# STM32Fx.net
KiCad netlist of a schematic drawn in Altium Designer
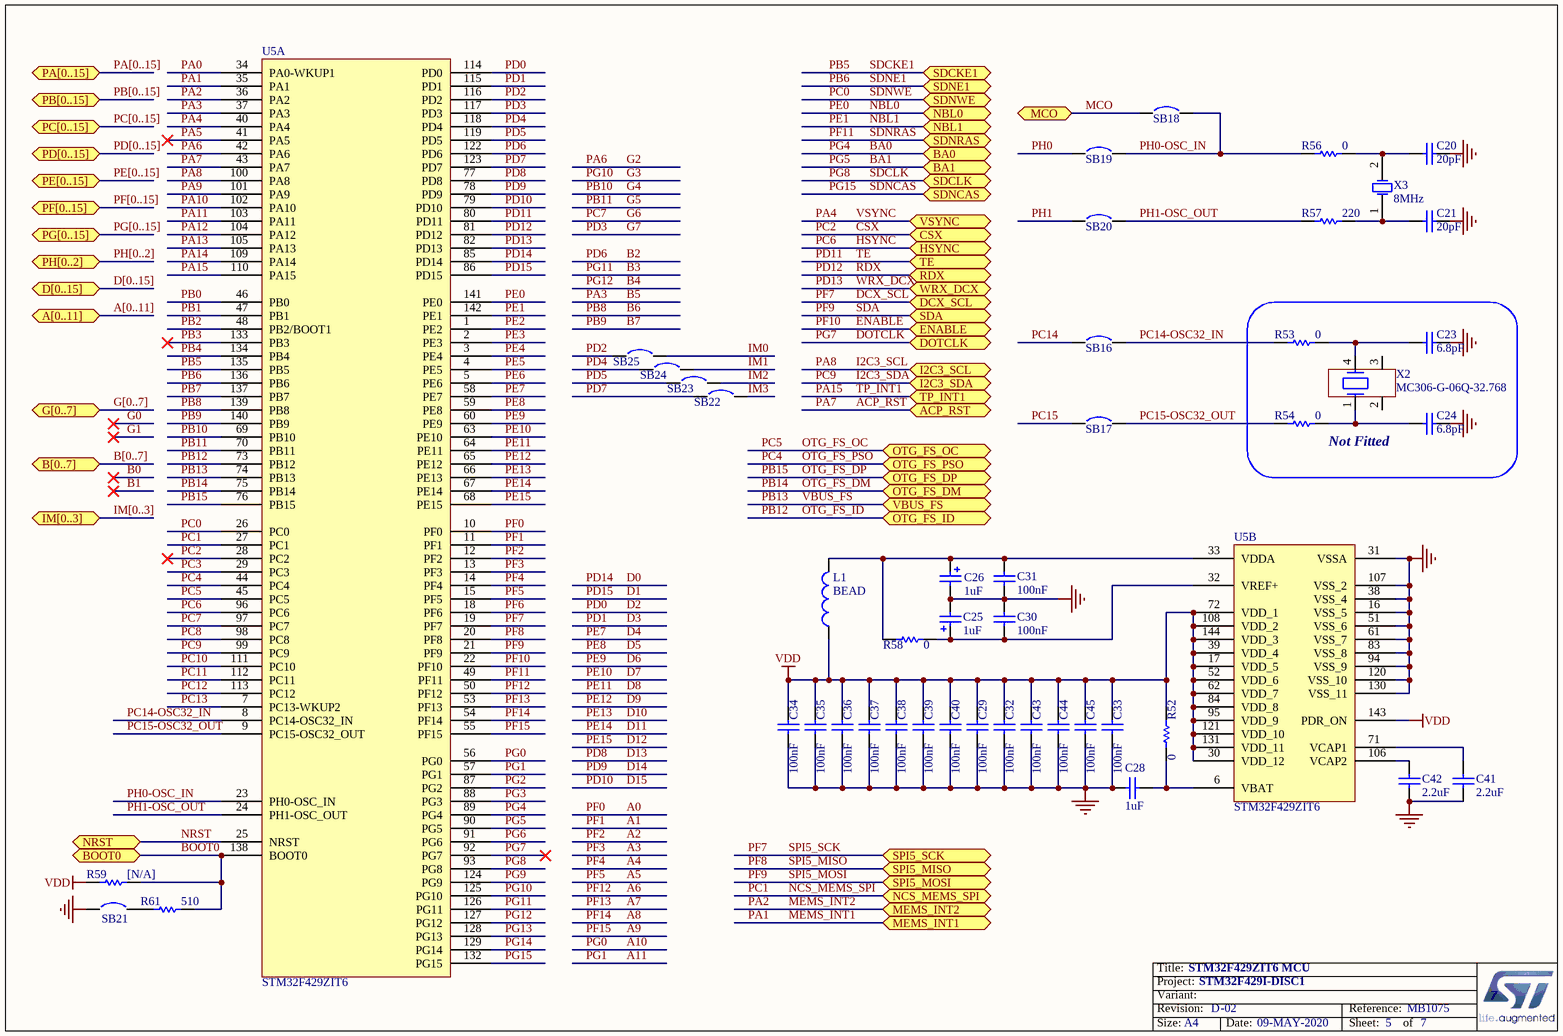
[diagram p0: STM32Fx.SchDoc]

(export (version "E")
  (design (tool "Eeschema 10.0.6"))
  (components
    (comp (ref "C20")
      (value "20pF")
      (footprint "0402C")
      (description "Capacitor 0402 / 0603 / 0805")
      (libsource (lib "MCD_TOOLS") (part "Capacitor_ST"))
    )
    (comp (ref "C21")
      (value "20pF")
      (footprint "0402C")
      (description "Capacitor 0402 / 0603 / 0805")
      (libsource (lib "MCD_TOOLS") (part "Capacitor_ST"))
    )
    (comp (ref "C23")
      (value "6.8pF")
      (footprint "0402C")
      (description "Capacitor 0402 / 0603 / 0805")
      (libsource (lib "MCD_TOOLS") (part "Capacitor_ST"))
    )
    (comp (ref "C24")
      (value "6.8pF")
      (footprint "0402C")
      (description "Capacitor 0402 / 0603 / 0805")
      (libsource (lib "MCD_TOOLS") (part "Capacitor_ST"))
    )
    (comp (ref "C25")
      (value "1uF")
      (footprint "TAN-A")
      (description "Polarized Capacitor (Radial)")
      (fields (field (name "PUBLISHER") "Altium Limited"))
      (libsource (lib "Miscellaneous Devices") (part "Cap Pol1"))
    )
    (comp (ref "C26")
      (value "1uF")
      (footprint "TAN-A")
      (description "Polarized Capacitor (Radial)")
      (fields (field (name "PUBLISHER") "Altium Limited"))
      (libsource (lib "Miscellaneous Devices") (part "Cap Pol1"))
    )
    (comp (ref "C28")
      (value "1uF")
      (footprint "0603C")
      (description "Capacitor 0402 / 0603 / 0805")
      (libsource (lib "MCD_TOOLS") (part "Capacitor_ST"))
    )
    (comp (ref "C29")
      (value "100nF")
      (footprint "0402C")
      (description "Capacitor 0402 / 0603 / 0805")
      (libsource (lib "MCD_TOOLS") (part "Capacitor_ST"))
    )
    (comp (ref "C30")
      (value "100nF")
      (footprint "0402C")
      (description "Capacitor 0402 / 0603 / 0805")
      (libsource (lib "MCD_TOOLS") (part "Capacitor_ST"))
    )
    (comp (ref "C31")
      (value "100nF")
      (footprint "0402C")
      (description "Capacitor 0402 / 0603 / 0805")
      (libsource (lib "MCD_TOOLS") (part "Capacitor_ST"))
    )
    (comp (ref "C32")
      (value "100nF")
      (footprint "0402C")
      (description "Capacitor 0402 / 0603 / 0805")
      (libsource (lib "MCD_TOOLS") (part "Capacitor_ST"))
    )
    (comp (ref "C33")
      (value "100nF")
      (footprint "0402C")
      (description "Capacitor 0402 / 0603 / 0805")
      (libsource (lib "MCD_TOOLS") (part "Capacitor_ST"))
    )
    (comp (ref "C34")
      (value "100nF")
      (footprint "0402C")
      (description "Capacitor 0402 / 0603 / 0805")
      (libsource (lib "MCD_TOOLS") (part "Capacitor_ST"))
    )
    (comp (ref "C35")
      (value "100nF")
      (footprint "0402C")
      (description "Capacitor 0402 / 0603 / 0805")
      (libsource (lib "MCD_TOOLS") (part "Capacitor_ST"))
    )
    (comp (ref "C36")
      (value "100nF")
      (footprint "0402C")
      (description "Capacitor 0402 / 0603 / 0805")
      (libsource (lib "MCD_TOOLS") (part "Capacitor_ST"))
    )
    (comp (ref "C37")
      (value "100nF")
      (footprint "0402C")
      (description "Capacitor 0402 / 0603 / 0805")
      (libsource (lib "MCD_TOOLS") (part "Capacitor_ST"))
    )
    (comp (ref "C38")
      (value "100nF")
      (footprint "0402C")
      (description "Capacitor 0402 / 0603 / 0805")
      (libsource (lib "MCD_TOOLS") (part "Capacitor_ST"))
    )
    (comp (ref "C39")
      (value "100nF")
      (footprint "0402C")
      (description "Capacitor 0402 / 0603 / 0805")
      (libsource (lib "MCD_TOOLS") (part "Capacitor_ST"))
    )
    (comp (ref "C40")
      (value "100nF")
      (footprint "0402C")
      (description "Capacitor 0402 / 0603 / 0805")
      (libsource (lib "MCD_TOOLS") (part "Capacitor_ST"))
    )
    (comp (ref "C41")
      (value "2.2uF")
      (footprint "TAN-A")
      (description "Low ESR Ceramic Capacitor (X7R)")
      (libsource (lib "MCD_TOOLS") (part "Cap Low ESR"))
    )
    (comp (ref "C42")
      (value "2.2uF")
      (footprint "TAN-A")
      (description "Low ESR Ceramic Capacitor (X7R)")
      (libsource (lib "MCD_TOOLS") (part "Cap Low ESR"))
    )
    (comp (ref "C43")
      (value "100nF")
      (footprint "0402C")
      (description "Capacitor 0402 / 0603 / 0805")
      (libsource (lib "MCD_TOOLS") (part "Capacitor_ST"))
    )
    (comp (ref "C44")
      (value "100nF")
      (footprint "0402C")
      (description "Capacitor 0402 / 0603 / 0805")
      (libsource (lib "MCD_TOOLS") (part "Capacitor_ST"))
    )
    (comp (ref "C45")
      (value "100nF")
      (footprint "0402C")
      (description "Capacitor 0402 / 0603 / 0805")
      (libsource (lib "MCD_TOOLS") (part "Capacitor_ST"))
    )
    (comp (ref "L1")
      (value "BEAD")
      (footprint "0603L")
      (description "Inductor")
      (fields (field (name "PUBLISHER") "Altium Limited"))
      (libsource (lib "MCD_TOOLS") (part "Inductor"))
    )
    (comp (ref "R52")
      (value "0")
      (footprint "0402R")
      (description "Resistor 0402 / 0603 / 0805")
      (libsource (lib "MCD_TOOLS") (part "Resistor_ST"))
    )
    (comp (ref "R53")
      (value "0")
      (footprint "0402R")
      (description "Resistor 0402 / 0603 / 0805")
      (libsource (lib "MCD_TOOLS") (part "Resistor_ST"))
    )
    (comp (ref "R54")
      (value "0")
      (footprint "0402R")
      (description "Resistor 0402 / 0603 / 0805")
      (libsource (lib "MCD_TOOLS") (part "Resistor_ST"))
    )
    (comp (ref "R56")
      (value "0")
      (footprint "0402R")
      (description "Resistor 0402 / 0603 / 0805")
      (libsource (lib "MCD_TOOLS") (part "Resistor_ST"))
    )
    (comp (ref "R57")
      (value "220")
      (footprint "0402R")
      (description "Resistor 0402 / 0603 / 0805")
      (libsource (lib "MCD_TOOLS") (part "Resistor_ST"))
    )
    (comp (ref "R58")
      (value "0")
      (footprint "0402R")
      (description "Resistor 0402 / 0603 / 0805")
      (libsource (lib "MCD_TOOLS") (part "Resistor_ST"))
    )
    (comp (ref "R59")
      (value "[N/A]")
      (footprint "0402R")
      (description "Resistor 0402 / 0603 / 0805")
      (libsource (lib "MCD_TOOLS") (part "Resistor_ST"))
    )
    (comp (ref "R61")
      (value "510")
      (footprint "0402R")
      (description "Resistor 0402 / 0603 / 0805")
      (libsource (lib "MCD_TOOLS") (part "Resistor_ST"))
    )
    (comp (ref "SB16")
      (value "Circuit Breaker")
      (footprint "JP2_SMD")
      (fields (field (name "PUBLISHER") "Altium Limited"))
      (libsource (lib "MB915") (part "Circuit Breaker"))
    )
    (comp (ref "SB17")
      (value "Circuit Breaker")
      (footprint "JP2_SMD")
      (fields (field (name "PUBLISHER") "Altium Limited"))
      (libsource (lib "MB915") (part "Circuit Breaker"))
    )
    (comp (ref "SB18")
      (value "Circuit Breaker")
      (footprint "JP2_SMD")
      (fields (field (name "PUBLISHER") "Altium Limited"))
      (libsource (lib "MB915") (part "Circuit Breaker"))
    )
    (comp (ref "SB19")
      (value "Circuit Breaker")
      (footprint "JP2_SMD")
      (fields (field (name "PUBLISHER") "Altium Limited"))
      (libsource (lib "MB915") (part "Circuit Breaker"))
    )
    (comp (ref "SB20")
      (value "Circuit Breaker")
      (footprint "JP2_SMD")
      (fields (field (name "PUBLISHER") "Altium Limited"))
      (libsource (lib "MB915") (part "Circuit Breaker"))
    )
    (comp (ref "SB21")
      (value "Circuit Breaker")
      (footprint "JP2_SMD")
      (fields (field (name "PUBLISHER") "Altium Limited"))
      (libsource (lib "MB915") (part "Circuit Breaker"))
    )
    (comp (ref "SB22")
      (value "Circuit Breaker")
      (footprint "JP2_SMD")
      (fields (field (name "PUBLISHER") "Altium Limited"))
      (libsource (lib "MB915") (part "Circuit Breaker"))
    )
    (comp (ref "SB23")
      (value "Circuit Breaker")
      (footprint "JP2_SMD")
      (fields (field (name "PUBLISHER") "Altium Limited"))
      (libsource (lib "MB915") (part "Circuit Breaker"))
    )
    (comp (ref "SB24")
      (value "Circuit Breaker")
      (footprint "JP2_SMD")
      (fields (field (name "PUBLISHER") "Altium Limited"))
      (libsource (lib "MB915") (part "Circuit Breaker"))
    )
    (comp (ref "SB25")
      (value "Circuit Breaker")
      (footprint "JP2_SMD")
      (fields (field (name "PUBLISHER") "Altium Limited"))
      (libsource (lib "MB915") (part "Circuit Breaker"))
    )
    (comp (ref "U5")
      (value "STM32F429ZIT6")
      (footprint "TQFP144")
      (description "STM32 Big Manta (STM32F429ZIT6U)")
      (libsource (lib "MCD_TOOLS") (part "STM32F429ZIT6U"))
    )
    (comp (ref "X2")
      (value "MC306-G-06Q-32.768")
      (footprint "MC306-CRYSTAL")
      (description "Crystal oscillator for clock,32.768K,6PF,20PPM,-40~85 degree,SMT")
      (libsource (lib "MCD_TOOLS") (part "XTAL_32K"))
    )
    (comp (ref "X3")
      (value "8MHz")
      (footprint "XTAL1")
      (description "Crystal Oscillator,8Mhz,20PF,20PPM,-10-70 degree,DIP,HC-49S")
      (libsource (lib "MCD_TOOLS") (part "XTAL"))
    )
  )
  (nets
    (net (code "5") (name "/B2") (class "Default")
      (node (ref "U5") (pin "122") (pinfunction "PD6_122") (pintype "passive"))
    )
    (net (code "6") (name "/B3") (class "Default")
      (node (ref "U5") (pin "126") (pinfunction "PG11_126") (pintype "passive"))
    )
    (net (code "7") (name "/B4") (class "Default")
      (node (ref "U5") (pin "127") (pinfunction "PG12_127") (pintype "passive"))
    )
    (net (code "8") (name "/B5") (class "Default")
      (node (ref "U5") (pin "37") (pinfunction "PA3_37") (pintype "passive"))
    )
    (net (code "9") (name "/B6") (class "Default")
      (node (ref "U5") (pin "139") (pinfunction "PB8_139") (pintype "passive"))
    )
    (net (code "10") (name "/B7") (class "Default")
      (node (ref "U5") (pin "140") (pinfunction "PB9_140") (pintype "passive"))
    )
    (net (code "11") (name "/BOOT0") (class "Default")
      (node (ref "R59") (pin "2") (pinfunction "2_2") (pintype "passive"))
      (node (ref "R61") (pin "2") (pinfunction "2_2") (pintype "passive"))
      (node (ref "U5") (pin "138") (pinfunction "BOOT0_138") (pintype "passive"))
    )
    (net (code "16") (name "/G2") (class "Default")
      (node (ref "U5") (pin "42") (pinfunction "PA6_42") (pintype "passive"))
    )
    (net (code "17") (name "/G3") (class "Default")
      (node (ref "U5") (pin "125") (pinfunction "PG10_125") (pintype "passive"))
    )
    (net (code "18") (name "/G4") (class "Default")
      (node (ref "U5") (pin "69") (pinfunction "PB10_69") (pintype "passive"))
    )
    (net (code "19") (name "/G5") (class "Default")
      (node (ref "U5") (pin "70") (pinfunction "PB11_70") (pintype "passive"))
    )
    (net (code "20") (name "/G6") (class "Default")
      (node (ref "U5") (pin "97") (pinfunction "PC7_97") (pintype "passive"))
    )
    (net (code "21") (name "/G7") (class "Default")
      (node (ref "U5") (pin "117") (pinfunction "PD3_117") (pintype "passive"))
    )
    (net (code "23") (name "/IM0") (class "Default")
      (node (ref "SB25") (pin "2") (pinfunction "2_2") (pintype "passive"))
    )
    (net (code "24") (name "/IM1") (class "Default")
      (node (ref "SB24") (pin "2") (pinfunction "2_2") (pintype "passive"))
    )
    (net (code "25") (name "/IM2") (class "Default")
      (node (ref "SB23") (pin "2") (pinfunction "2_2") (pintype "passive"))
    )
    (net (code "26") (name "/IM3") (class "Default")
      (node (ref "SB22") (pin "2") (pinfunction "2_2") (pintype "passive"))
    )
    (net (code "28") (name "/MCO") (class "Default")
      (node (ref "SB18") (pin "1") (pinfunction "1_1") (pintype "passive"))
    )
    (net (code "29") (name "/NRST") (class "Default")
      (node (ref "U5") (pin "25") (pinfunction "NRST_25") (pintype "passive"))
    )
    (net (code "30") (name "/PA0") (class "Default")
      (node (ref "U5") (pin "34") (pinfunction "PA0-WKUP1_34") (pintype "passive"))
    )
    (net (code "31") (name "/PA1") (class "Default")
      (node (ref "U5") (pin "35") (pinfunction "PA1_35") (pintype "passive"))
    )
    (net (code "32") (name "/PA2") (class "Default")
      (node (ref "U5") (pin "36") (pinfunction "PA2_36") (pintype "passive"))
    )
    (net (code "33") (name "/PA4") (class "Default")
      (node (ref "U5") (pin "40") (pinfunction "PA4_40") (pintype "passive"))
    )
    (net (code "34") (name "/PA5") (class "Default")
      (node (ref "U5") (pin "41") (pinfunction "PA5_41") (pintype "passive+no_connect"))
    )
    (net (code "35") (name "/PA7") (class "Default")
      (node (ref "U5") (pin "43") (pinfunction "PA7_43") (pintype "passive"))
    )
    (net (code "36") (name "/PA8") (class "Default")
      (node (ref "U5") (pin "100") (pinfunction "PA8_100") (pintype "passive"))
    )
    (net (code "37") (name "/PA9") (class "Default")
      (node (ref "U5") (pin "101") (pinfunction "PA9_101") (pintype "passive"))
    )
    (net (code "38") (name "/PA10") (class "Default")
      (node (ref "U5") (pin "102") (pinfunction "PA10_102") (pintype "passive"))
    )
    (net (code "39") (name "/PA11") (class "Default")
      (node (ref "U5") (pin "103") (pinfunction "PA11_103") (pintype "passive"))
    )
    (net (code "40") (name "/PA12") (class "Default")
      (node (ref "U5") (pin "104") (pinfunction "PA12_104") (pintype "passive"))
    )
    (net (code "41") (name "/PA13") (class "Default")
      (node (ref "U5") (pin "105") (pinfunction "PA13_105") (pintype "passive"))
    )
    (net (code "42") (name "/PA14") (class "Default")
      (node (ref "U5") (pin "109") (pinfunction "PA14_109") (pintype "passive"))
    )
    (net (code "43") (name "/PA15") (class "Default")
      (node (ref "U5") (pin "110") (pinfunction "PA15_110") (pintype "passive"))
    )
    (net (code "45") (name "/PB0") (class "Default")
      (node (ref "U5") (pin "46") (pinfunction "PB0_46") (pintype "passive"))
    )
    (net (code "46") (name "/PB1") (class "Default")
      (node (ref "U5") (pin "47") (pinfunction "PB1_47") (pintype "passive"))
    )
    (net (code "47") (name "/PB2") (class "Default")
      (node (ref "U5") (pin "48") (pinfunction "PB2/BOOT1_48") (pintype "passive"))
    )
    (net (code "48") (name "/PB3") (class "Default")
      (node (ref "U5") (pin "133") (pinfunction "PB3_133") (pintype "passive+no_connect"))
    )
    (net (code "49") (name "/PB4") (class "Default")
      (node (ref "U5") (pin "134") (pinfunction "PB4_134") (pintype "passive"))
    )
    (net (code "50") (name "/PB5") (class "Default")
      (node (ref "U5") (pin "135") (pinfunction "PB5_135") (pintype "passive"))
    )
    (net (code "51") (name "/PB6") (class "Default")
      (node (ref "U5") (pin "136") (pinfunction "PB6_136") (pintype "passive"))
    )
    (net (code "52") (name "/PB7") (class "Default")
      (node (ref "U5") (pin "137") (pinfunction "PB7_137") (pintype "passive"))
    )
    (net (code "53") (name "/PB12") (class "Default")
      (node (ref "U5") (pin "73") (pinfunction "PB12_73") (pintype "passive"))
    )
    (net (code "54") (name "/PB13") (class "Default")
      (node (ref "U5") (pin "74") (pinfunction "PB13_74") (pintype "passive"))
    )
    (net (code "55") (name "/PB14") (class "Default")
      (node (ref "U5") (pin "75") (pinfunction "PB14_75") (pintype "passive"))
    )
    (net (code "56") (name "/PB15") (class "Default")
      (node (ref "U5") (pin "76") (pinfunction "PB15_76") (pintype "passive"))
    )
    (net (code "58") (name "/PC0") (class "Default")
      (node (ref "U5") (pin "26") (pinfunction "PC0_26") (pintype "passive"))
    )
    (net (code "59") (name "/PC1") (class "Default")
      (node (ref "U5") (pin "27") (pinfunction "PC1_27") (pintype "passive"))
    )
    (net (code "60") (name "/PC2") (class "Default")
      (node (ref "U5") (pin "28") (pinfunction "PC2_28") (pintype "passive+no_connect"))
    )
    (net (code "61") (name "/PC3") (class "Default")
      (node (ref "U5") (pin "29") (pinfunction "PC3_29") (pintype "passive"))
    )
    (net (code "62") (name "/PC4") (class "Default")
      (node (ref "U5") (pin "44") (pinfunction "PC4_44") (pintype "passive"))
    )
    (net (code "63") (name "/PC5") (class "Default")
      (node (ref "U5") (pin "45") (pinfunction "PC5_45") (pintype "passive"))
    )
    (net (code "64") (name "/PC6") (class "Default")
      (node (ref "U5") (pin "96") (pinfunction "PC6_96") (pintype "passive"))
    )
    (net (code "65") (name "/PC8") (class "Default")
      (node (ref "U5") (pin "98") (pinfunction "PC8_98") (pintype "passive"))
    )
    (net (code "66") (name "/PC9") (class "Default")
      (node (ref "U5") (pin "99") (pinfunction "PC9_99") (pintype "passive"))
    )
    (net (code "67") (name "/PC10") (class "Default")
      (node (ref "U5") (pin "111") (pinfunction "PC10_111") (pintype "passive"))
    )
    (net (code "68") (name "/PC11") (class "Default")
      (node (ref "U5") (pin "112") (pinfunction "PC11_112") (pintype "passive"))
    )
    (net (code "69") (name "/PC12") (class "Default")
      (node (ref "U5") (pin "113") (pinfunction "PC12_113") (pintype "passive"))
    )
    (net (code "70") (name "/PC13") (class "Default")
      (node (ref "U5") (pin "7") (pinfunction "PC13-WKUP2_7") (pintype "passive"))
    )
    (net (code "71") (name "/PC14") (class "Default")
      (node (ref "SB16") (pin "1") (pinfunction "1_1") (pintype "passive"))
    )
    (net (code "72") (name "/PC14-OSC32_IN") (class "Default")
      (node (ref "R53") (pin "1") (pinfunction "1_1") (pintype "passive"))
      (node (ref "SB16") (pin "2") (pinfunction "2_2") (pintype "passive"))
      (node (ref "U5") (pin "8") (pinfunction "PC14-OSC32_IN_8") (pintype "passive"))
    )
    (net (code "73") (name "/PC15") (class "Default")
      (node (ref "SB17") (pin "1") (pinfunction "1_1") (pintype "passive"))
    )
    (net (code "74") (name "/PC15-OSC32_OUT") (class "Default")
      (node (ref "R54") (pin "1") (pinfunction "1_1") (pintype "passive"))
      (node (ref "SB17") (pin "2") (pinfunction "2_2") (pintype "passive"))
      (node (ref "U5") (pin "9") (pinfunction "PC15-OSC32_OUT_9") (pintype "passive"))
    )
    (net (code "76") (name "/PD0") (class "Default")
      (node (ref "U5") (pin "114") (pinfunction "PD0_114") (pintype "passive"))
    )
    (net (code "77") (name "/PD1") (class "Default")
      (node (ref "U5") (pin "115") (pinfunction "PD1_115") (pintype "passive"))
    )
    (net (code "78") (name "/PD2") (class "Default")
      (node (ref "SB25") (pin "1") (pinfunction "1_1") (pintype "passive"))
      (node (ref "U5") (pin "116") (pinfunction "PD2_116") (pintype "passive"))
    )
    (net (code "79") (name "/PD4") (class "Default")
      (node (ref "SB24") (pin "1") (pinfunction "1_1") (pintype "passive"))
      (node (ref "U5") (pin "118") (pinfunction "PD4_118") (pintype "passive"))
    )
    (net (code "80") (name "/PD5") (class "Default")
      (node (ref "SB23") (pin "1") (pinfunction "1_1") (pintype "passive"))
      (node (ref "U5") (pin "119") (pinfunction "PD5_119") (pintype "passive"))
    )
    (net (code "81") (name "/PD7") (class "Default")
      (node (ref "SB22") (pin "1") (pinfunction "1_1") (pintype "passive"))
      (node (ref "U5") (pin "123") (pinfunction "PD7_123") (pintype "passive"))
    )
    (net (code "82") (name "/PD8") (class "Default")
      (node (ref "U5") (pin "77") (pinfunction "PD8_77") (pintype "passive"))
    )
    (net (code "83") (name "/PD9") (class "Default")
      (node (ref "U5") (pin "78") (pinfunction "PD9_78") (pintype "passive"))
    )
    (net (code "84") (name "/PD10") (class "Default")
      (node (ref "U5") (pin "79") (pinfunction "PD10_79") (pintype "passive"))
    )
    (net (code "85") (name "/PD11") (class "Default")
      (node (ref "U5") (pin "80") (pinfunction "PD11_80") (pintype "passive"))
    )
    (net (code "86") (name "/PD12") (class "Default")
      (node (ref "U5") (pin "81") (pinfunction "PD12_81") (pintype "passive"))
    )
    (net (code "87") (name "/PD13") (class "Default")
      (node (ref "U5") (pin "82") (pinfunction "PD13_82") (pintype "passive"))
    )
    (net (code "88") (name "/PD14") (class "Default")
      (node (ref "U5") (pin "85") (pinfunction "PD14_85") (pintype "passive"))
    )
    (net (code "89") (name "/PD15") (class "Default")
      (node (ref "U5") (pin "86") (pinfunction "PD15_86") (pintype "passive"))
    )
    (net (code "91") (name "/PE0") (class "Default")
      (node (ref "U5") (pin "141") (pinfunction "PE0_141") (pintype "passive"))
    )
    (net (code "92") (name "/PE1") (class "Default")
      (node (ref "U5") (pin "142") (pinfunction "PE1_142") (pintype "passive"))
    )
    (net (code "93") (name "/PE2") (class "Default")
      (node (ref "U5") (pin "1") (pinfunction "PE2_1") (pintype "passive"))
    )
    (net (code "94") (name "/PE3") (class "Default")
      (node (ref "U5") (pin "2") (pinfunction "PE3_2") (pintype "passive"))
    )
    (net (code "95") (name "/PE4") (class "Default")
      (node (ref "U5") (pin "3") (pinfunction "PE4_3") (pintype "passive"))
    )
    (net (code "96") (name "/PE5") (class "Default")
      (node (ref "U5") (pin "4") (pinfunction "PE5_4") (pintype "passive"))
    )
    (net (code "97") (name "/PE6") (class "Default")
      (node (ref "U5") (pin "5") (pinfunction "PE6_5") (pintype "passive"))
    )
    (net (code "98") (name "/PE7") (class "Default")
      (node (ref "U5") (pin "58") (pinfunction "PE7_58") (pintype "passive"))
    )
    (net (code "99") (name "/PE8") (class "Default")
      (node (ref "U5") (pin "59") (pinfunction "PE8_59") (pintype "passive"))
    )
    (net (code "100") (name "/PE9") (class "Default")
      (node (ref "U5") (pin "60") (pinfunction "PE9_60") (pintype "passive"))
    )
    (net (code "101") (name "/PE10") (class "Default")
      (node (ref "U5") (pin "63") (pinfunction "PE10_63") (pintype "passive"))
    )
    (net (code "102") (name "/PE11") (class "Default")
      (node (ref "U5") (pin "64") (pinfunction "PE11_64") (pintype "passive"))
    )
    (net (code "103") (name "/PE12") (class "Default")
      (node (ref "U5") (pin "65") (pinfunction "PE12_65") (pintype "passive"))
    )
    (net (code "104") (name "/PE13") (class "Default")
      (node (ref "U5") (pin "66") (pinfunction "PE13_66") (pintype "passive"))
    )
    (net (code "105") (name "/PE14") (class "Default")
      (node (ref "U5") (pin "67") (pinfunction "PE14_67") (pintype "passive"))
    )
    (net (code "106") (name "/PE15") (class "Default")
      (node (ref "U5") (pin "68") (pinfunction "PE15_68") (pintype "passive"))
    )
    (net (code "108") (name "/PF0") (class "Default")
      (node (ref "U5") (pin "10") (pinfunction "PF0_10") (pintype "passive"))
    )
    (net (code "109") (name "/PF1") (class "Default")
      (node (ref "U5") (pin "11") (pinfunction "PF1_11") (pintype "passive"))
    )
    (net (code "110") (name "/PF2") (class "Default")
      (node (ref "U5") (pin "12") (pinfunction "PF2_12") (pintype "passive"))
    )
    (net (code "111") (name "/PF3") (class "Default")
      (node (ref "U5") (pin "13") (pinfunction "PF3_13") (pintype "passive"))
    )
    (net (code "112") (name "/PF4") (class "Default")
      (node (ref "U5") (pin "14") (pinfunction "PF4_14") (pintype "passive"))
    )
    (net (code "113") (name "/PF5") (class "Default")
      (node (ref "U5") (pin "15") (pinfunction "PF5_15") (pintype "passive"))
    )
    (net (code "114") (name "/PF6") (class "Default")
      (node (ref "U5") (pin "18") (pinfunction "PF6_18") (pintype "passive"))
    )
    (net (code "115") (name "/PF7") (class "Default")
      (node (ref "U5") (pin "19") (pinfunction "PF7_19") (pintype "passive"))
    )
    (net (code "116") (name "/PF8") (class "Default")
      (node (ref "U5") (pin "20") (pinfunction "PF8_20") (pintype "passive"))
    )
    (net (code "117") (name "/PF9") (class "Default")
      (node (ref "U5") (pin "21") (pinfunction "PF9_21") (pintype "passive"))
    )
    (net (code "118") (name "/PF10") (class "Default")
      (node (ref "U5") (pin "22") (pinfunction "PF10_22") (pintype "passive"))
    )
    (net (code "119") (name "/PF11") (class "Default")
      (node (ref "U5") (pin "49") (pinfunction "PF11_49") (pintype "passive"))
    )
    (net (code "120") (name "/PF12") (class "Default")
      (node (ref "U5") (pin "50") (pinfunction "PF12_50") (pintype "passive"))
    )
    (net (code "121") (name "/PF13") (class "Default")
      (node (ref "U5") (pin "53") (pinfunction "PF13_53") (pintype "passive"))
    )
    (net (code "122") (name "/PF14") (class "Default")
      (node (ref "U5") (pin "54") (pinfunction "PF14_54") (pintype "passive"))
    )
    (net (code "123") (name "/PF15") (class "Default")
      (node (ref "U5") (pin "55") (pinfunction "PF15_55") (pintype "passive"))
    )
    (net (code "125") (name "/PG0") (class "Default")
      (node (ref "U5") (pin "56") (pinfunction "PG0_56") (pintype "passive"))
    )
    (net (code "126") (name "/PG1") (class "Default")
      (node (ref "U5") (pin "57") (pinfunction "PG1_57") (pintype "passive"))
    )
    (net (code "127") (name "/PG2") (class "Default")
      (node (ref "U5") (pin "87") (pinfunction "PG2_87") (pintype "passive"))
    )
    (net (code "128") (name "/PG3") (class "Default")
      (node (ref "U5") (pin "88") (pinfunction "PG3_88") (pintype "passive"))
    )
    (net (code "129") (name "/PG4") (class "Default")
      (node (ref "U5") (pin "89") (pinfunction "PG4_89") (pintype "passive"))
    )
    (net (code "130") (name "/PG5") (class "Default")
      (node (ref "U5") (pin "90") (pinfunction "PG5_90") (pintype "passive"))
    )
    (net (code "131") (name "/PG6") (class "Default")
      (node (ref "U5") (pin "91") (pinfunction "PG6_91") (pintype "passive"))
    )
    (net (code "132") (name "/PG7") (class "Default")
      (node (ref "U5") (pin "92") (pinfunction "PG7_92") (pintype "passive+no_connect"))
    )
    (net (code "133") (name "/PG8") (class "Default")
      (node (ref "U5") (pin "93") (pinfunction "PG8_93") (pintype "passive"))
    )
    (net (code "134") (name "/PG9") (class "Default")
      (node (ref "U5") (pin "124") (pinfunction "PG9_124") (pintype "passive"))
    )
    (net (code "135") (name "/PG13") (class "Default")
      (node (ref "U5") (pin "128") (pinfunction "PG13_128") (pintype "passive"))
    )
    (net (code "136") (name "/PG14") (class "Default")
      (node (ref "U5") (pin "129") (pinfunction "PG14_129") (pintype "passive"))
    )
    (net (code "137") (name "/PG15") (class "Default")
      (node (ref "U5") (pin "132") (pinfunction "PG15_132") (pintype "passive"))
    )
    (net (code "139") (name "/PH0") (class "Default")
      (node (ref "SB19") (pin "1") (pinfunction "1_1") (pintype "passive"))
    )
    (net (code "140") (name "/PH0-OSC_IN") (class "Default")
      (node (ref "R56") (pin "1") (pinfunction "1_1") (pintype "passive"))
      (node (ref "SB18") (pin "2") (pinfunction "2_2") (pintype "passive"))
      (node (ref "SB19") (pin "2") (pinfunction "2_2") (pintype "passive"))
      (node (ref "U5") (pin "23") (pinfunction "PH0-OSC_IN_23") (pintype "passive"))
    )
    (net (code "141") (name "/PH1") (class "Default")
      (node (ref "SB20") (pin "1") (pinfunction "1_1") (pintype "passive"))
    )
    (net (code "142") (name "/PH1-OSC_OUT") (class "Default")
      (node (ref "R57") (pin "1") (pinfunction "1_1") (pintype "passive"))
      (node (ref "SB20") (pin "2") (pinfunction "2_2") (pintype "passive"))
      (node (ref "U5") (pin "24") (pinfunction "PH1-OSC_OUT_24") (pintype "passive"))
    )
    (net (code "144") (name "GND") (class "Default")
      (node (ref "C20") (pin "2") (pinfunction "2_2") (pintype "passive"))
      (node (ref "C21") (pin "2") (pinfunction "2_2") (pintype "passive"))
      (node (ref "C23") (pin "2") (pinfunction "2_2") (pintype "passive"))
      (node (ref "C24") (pin "2") (pinfunction "2_2") (pintype "passive"))
      (node (ref "C25") (pin "2") (pinfunction "2_2") (pintype "passive"))
      (node (ref "C26") (pin "2") (pinfunction "2_2") (pintype "passive"))
      (node (ref "C28") (pin "1") (pinfunction "1_1") (pintype "passive"))
      (node (ref "C29") (pin "1") (pinfunction "1_1") (pintype "passive"))
      (node (ref "C30") (pin "2") (pinfunction "2_2") (pintype "passive"))
      (node (ref "C31") (pin "1") (pinfunction "1_1") (pintype "passive"))
      (node (ref "C32") (pin "1") (pinfunction "1_1") (pintype "passive"))
      (node (ref "C33") (pin "1") (pinfunction "1_1") (pintype "passive"))
      (node (ref "C34") (pin "1") (pinfunction "1_1") (pintype "passive"))
      (node (ref "C35") (pin "1") (pinfunction "1_1") (pintype "passive"))
      (node (ref "C36") (pin "1") (pinfunction "1_1") (pintype "passive"))
      (node (ref "C37") (pin "1") (pinfunction "1_1") (pintype "passive"))
      (node (ref "C38") (pin "1") (pinfunction "1_1") (pintype "passive"))
      (node (ref "C39") (pin "1") (pinfunction "1_1") (pintype "passive"))
      (node (ref "C40") (pin "1") (pinfunction "1_1") (pintype "passive"))
      (node (ref "C41") (pin "2") (pinfunction "2_2") (pintype "passive"))
      (node (ref "C42") (pin "2") (pinfunction "2_2") (pintype "passive"))
      (node (ref "C43") (pin "1") (pinfunction "1_1") (pintype "passive"))
      (node (ref "C44") (pin "1") (pinfunction "1_1") (pintype "passive"))
      (node (ref "C45") (pin "1") (pinfunction "1_1") (pintype "passive"))
      (node (ref "SB21") (pin "1") (pinfunction "1_1") (pintype "passive"))
      (node (ref "U5") (pin "107") (pinfunction "VSS_2_107") (pintype "passive"))
      (node (ref "U5") (pin "120") (pinfunction "VSS_10_120") (pintype "passive"))
      (node (ref "U5") (pin "130") (pinfunction "VSS_11_130") (pintype "passive"))
      (node (ref "U5") (pin "16") (pinfunction "VSS_5_16") (pintype "passive"))
      (node (ref "U5") (pin "31") (pinfunction "VSSA_31") (pintype "passive"))
      (node (ref "U5") (pin "38") (pinfunction "VSS_4_38") (pintype "passive"))
      (node (ref "U5") (pin "51") (pinfunction "VSS_6_51") (pintype "passive"))
      (node (ref "U5") (pin "61") (pinfunction "VSS_7_61") (pintype "passive"))
      (node (ref "U5") (pin "83") (pinfunction "VSS_8_83") (pintype "passive"))
      (node (ref "U5") (pin "94") (pinfunction "VSS_9_94") (pintype "passive"))
    )
    (net (code "145") (name "Net-(C23-Pad1)") (class "Default")
      (node (ref "C23") (pin "1") (pinfunction "1_1") (pintype "passive"))
      (node (ref "R53") (pin "2") (pinfunction "2_2") (pintype "passive"))
      (node (ref "X2") (pin "4") (pinfunction "4_4") (pintype "passive"))
    )
    (net (code "146") (name "Net-(C24-Pad1)") (class "Default")
      (node (ref "C24") (pin "1") (pinfunction "1_1") (pintype "passive"))
      (node (ref "R54") (pin "2") (pinfunction "2_2") (pintype "passive"))
      (node (ref "X2") (pin "1") (pinfunction "1_1") (pintype "passive"))
    )
    (net (code "147") (name "Net-(R61-Pad1)") (class "Default")
      (node (ref "R61") (pin "1") (pinfunction "1_1") (pintype "passive"))
      (node (ref "SB21") (pin "2") (pinfunction "2_2") (pintype "passive"))
    )
    (net (code "148") (name "Net-(U5B-VBAT)") (class "Default")
      (node (ref "C28") (pin "2") (pinfunction "2_2") (pintype "passive"))
      (node (ref "R52") (pin "1") (pinfunction "1_1") (pintype "passive"))
      (node (ref "U5") (pin "6") (pinfunction "VBAT_6") (pintype "passive"))
    )
    (net (code "149") (name "Net-(U5B-VCAP1)") (class "Default")
      (node (ref "C41") (pin "1") (pinfunction "1_1") (pintype "passive"))
      (node (ref "U5") (pin "71") (pinfunction "VCAP1_71") (pintype "passive"))
    )
    (net (code "150") (name "Net-(U5B-VCAP2)") (class "Default")
      (node (ref "C42") (pin "1") (pinfunction "1_1") (pintype "passive"))
      (node (ref "U5") (pin "106") (pinfunction "VCAP2_106") (pintype "passive"))
    )
    (net (code "151") (name "Net-(U5B-VDDA)") (class "Default")
      (node (ref "C26") (pin "1") (pinfunction "1_1") (pintype "passive"))
      (node (ref "C31") (pin "2") (pinfunction "2_2") (pintype "passive"))
      (node (ref "L1") (pin "2") (pinfunction "2_2") (pintype "passive"))
      (node (ref "R58") (pin "1") (pinfunction "1_1") (pintype "passive"))
      (node (ref "U5") (pin "33") (pinfunction "VDDA_33") (pintype "passive"))
    )
    (net (code "152") (name "Net-(U5B-VREF+)") (class "Default")
      (node (ref "C25") (pin "1") (pinfunction "1_1") (pintype "passive"))
      (node (ref "C30") (pin "1") (pinfunction "1_1") (pintype "passive"))
      (node (ref "R58") (pin "2") (pinfunction "2_2") (pintype "passive"))
      (node (ref "U5") (pin "32") (pinfunction "VREF+_32") (pintype "passive"))
    )
    (net (code "153") (name "Net-(X3-OSC1)") (class "Default")
      (node (ref "C21") (pin "1") (pinfunction "1_1") (pintype "passive"))
      (node (ref "R57") (pin "2") (pinfunction "2_2") (pintype "passive"))
      (node (ref "X3") (pin "1") (pinfunction "OSC1_1") (pintype "passive"))
    )
    (net (code "154") (name "Net-(X3-OSC2)") (class "Default")
      (node (ref "C20") (pin "1") (pinfunction "1_1") (pintype "passive"))
      (node (ref "R56") (pin "2") (pinfunction "2_2") (pintype "passive"))
      (node (ref "X3") (pin "2") (pinfunction "OSC2_2") (pintype "passive"))
    )
    (net (code "155") (name "VDD") (class "Default")
      (node (ref "C29") (pin "2") (pinfunction "2_2") (pintype "passive"))
      (node (ref "C32") (pin "2") (pinfunction "2_2") (pintype "passive"))
      (node (ref "C33") (pin "2") (pinfunction "2_2") (pintype "passive"))
      (node (ref "C34") (pin "2") (pinfunction "2_2") (pintype "passive"))
      (node (ref "C35") (pin "2") (pinfunction "2_2") (pintype "passive"))
      (node (ref "C36") (pin "2") (pinfunction "2_2") (pintype "passive"))
      (node (ref "C37") (pin "2") (pinfunction "2_2") (pintype "passive"))
      (node (ref "C38") (pin "2") (pinfunction "2_2") (pintype "passive"))
      (node (ref "C39") (pin "2") (pinfunction "2_2") (pintype "passive"))
      (node (ref "C40") (pin "2") (pinfunction "2_2") (pintype "passive"))
      (node (ref "C43") (pin "2") (pinfunction "2_2") (pintype "passive"))
      (node (ref "C44") (pin "2") (pinfunction "2_2") (pintype "passive"))
      (node (ref "C45") (pin "2") (pinfunction "2_2") (pintype "passive"))
      (node (ref "L1") (pin "1") (pinfunction "1_1") (pintype "passive"))
      (node (ref "R52") (pin "2") (pinfunction "2_2") (pintype "passive"))
      (node (ref "R59") (pin "1") (pinfunction "1_1") (pintype "passive"))
      (node (ref "U5") (pin "108") (pinfunction "VDD_2_108") (pintype "passive"))
      (node (ref "U5") (pin "121") (pinfunction "VDD_10_121") (pintype "passive"))
      (node (ref "U5") (pin "131") (pinfunction "VDD_11_131") (pintype "passive"))
      (node (ref "U5") (pin "143") (pinfunction "PDR_ON_143") (pintype "passive"))
      (node (ref "U5") (pin "144") (pinfunction "VDD_3_144") (pintype "passive"))
      (node (ref "U5") (pin "17") (pinfunction "VDD_5_17") (pintype "passive"))
      (node (ref "U5") (pin "30") (pinfunction "VDD_12_30") (pintype "passive"))
      (node (ref "U5") (pin "39") (pinfunction "VDD_4_39") (pintype "passive"))
      (node (ref "U5") (pin "52") (pinfunction "VDD_6_52") (pintype "passive"))
      (node (ref "U5") (pin "62") (pinfunction "VDD_7_62") (pintype "passive"))
      (node (ref "U5") (pin "72") (pinfunction "VDD_1_72") (pintype "passive"))
      (node (ref "U5") (pin "84") (pinfunction "VDD_8_84") (pintype "passive"))
      (node (ref "U5") (pin "95") (pinfunction "VDD_9_95") (pintype "passive"))
    )
    (net (code "156") (name "unconnected-(X2-Pad2)") (class "Default")
      (node (ref "X2") (pin "2") (pinfunction "2_2") (pintype "passive"))
    )
    (net (code "157") (name "unconnected-(X2-Pad3)") (class "Default")
      (node (ref "X2") (pin "3") (pinfunction "3_3") (pintype "passive"))
    )
  )
)
